# final_mouse.net
KiCad netlist of a schematic drawn in EAGLE
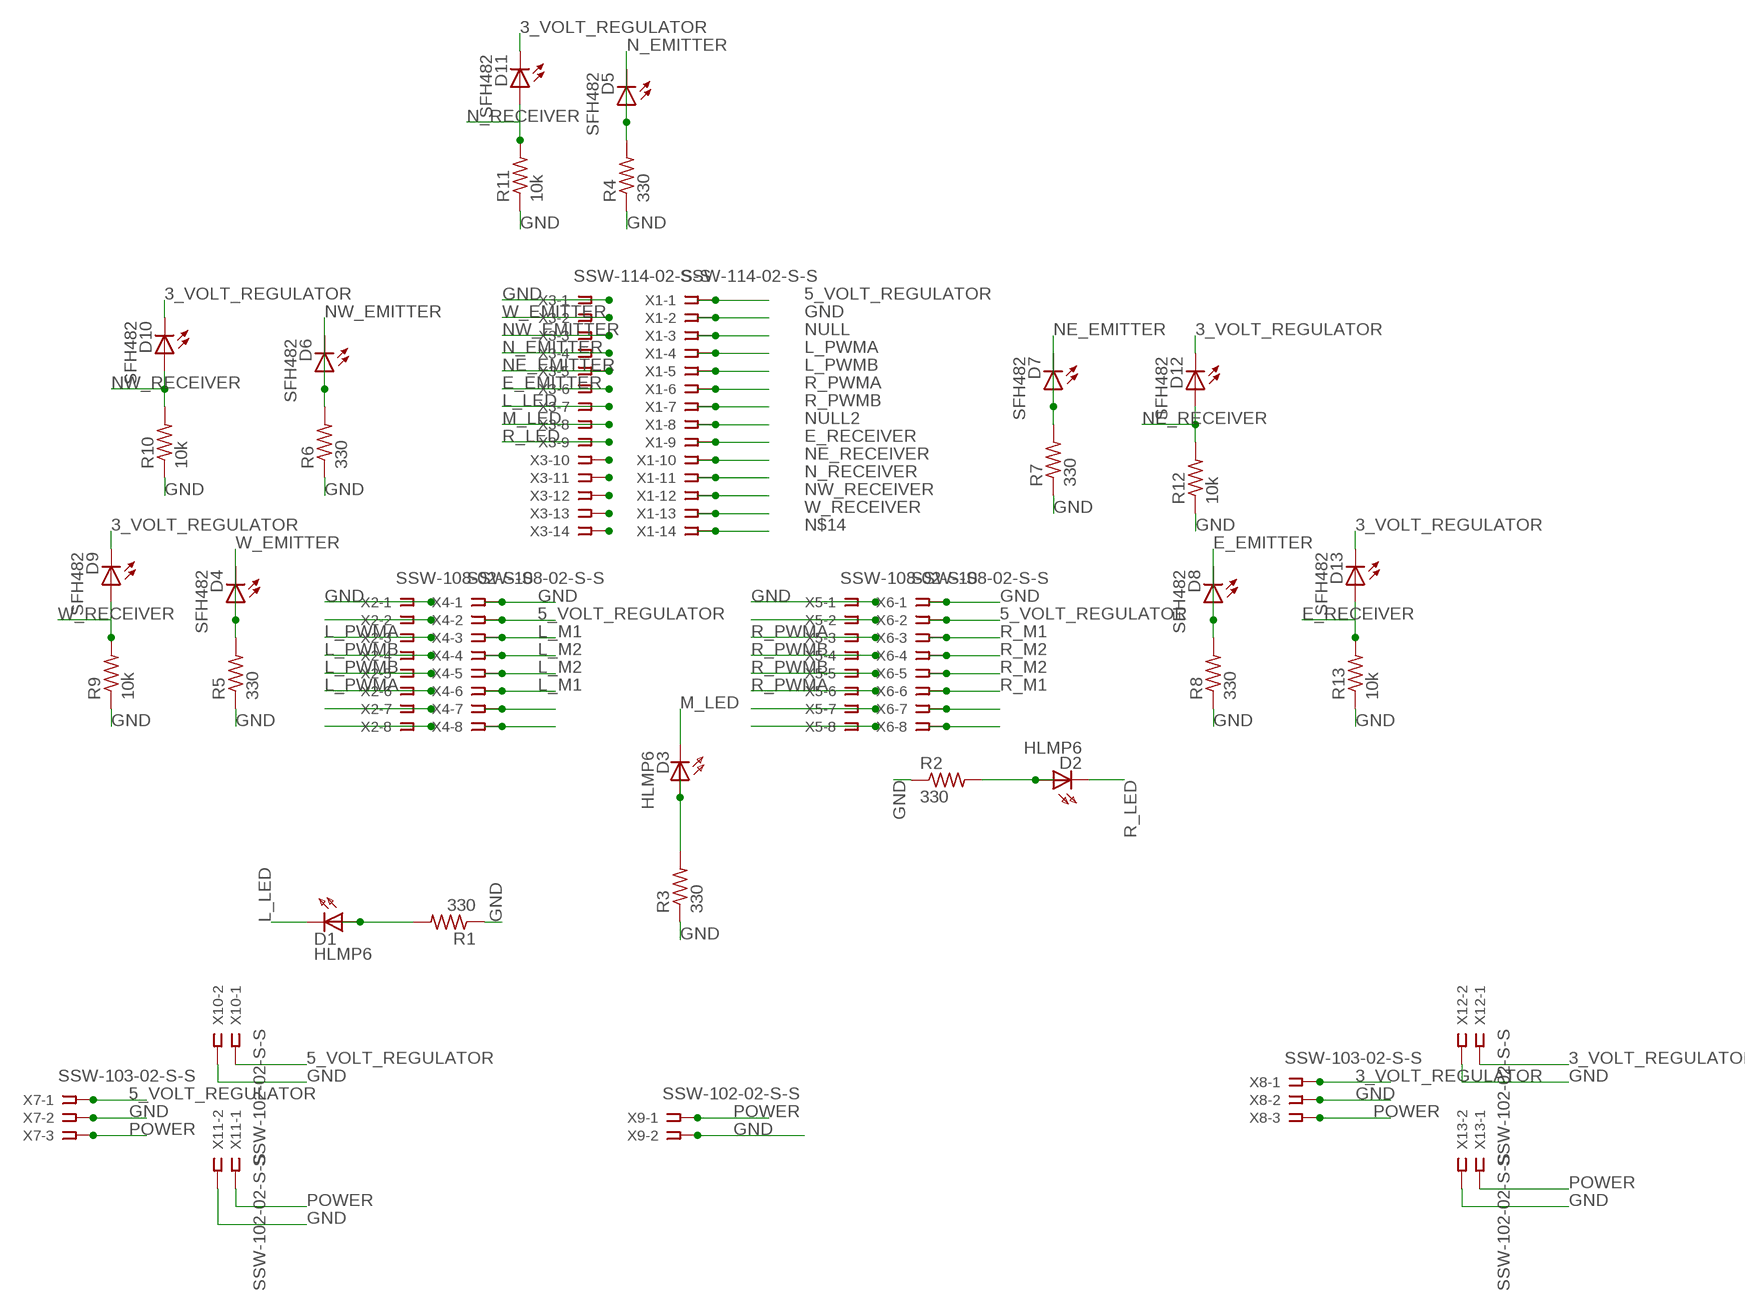
[diagram p0: schematic, sheet 1]

(export (version "E")
  (design (tool "Eeschema 10.0.6"))
  (components
    (comp (ref "D1")
      (value "HLMP6")
      (footprint "eagle-import:HLMP6")
      (fields (field (name "MF") "AGILENT TECHNOLOGIES") (field (name "MPN") "HLMP-6500"))
      (libsource (lib "eagle-import") (part "HLMP6"))
    )
    (comp (ref "D2")
      (value "HLMP6")
      (footprint "eagle-import:HLMP6")
      (fields (field (name "MF") "AGILENT TECHNOLOGIES") (field (name "MPN") "HLMP-6500"))
      (libsource (lib "eagle-import") (part "HLMP6"))
    )
    (comp (ref "D3")
      (value "HLMP6")
      (footprint "eagle-import:HLMP6")
      (fields (field (name "MF") "AGILENT TECHNOLOGIES") (field (name "MPN") "HLMP-6500"))
      (libsource (lib "eagle-import") (part "HLMP6"))
    )
    (comp (ref "D4")
      (value "SFH482")
      (footprint "eagle-import:SFH482")
      (libsource (lib "eagle-import") (part "SFH482"))
    )
    (comp (ref "D5")
      (value "SFH482")
      (footprint "eagle-import:SFH482")
      (libsource (lib "eagle-import") (part "SFH482"))
    )
    (comp (ref "D6")
      (value "SFH482")
      (footprint "eagle-import:SFH482")
      (libsource (lib "eagle-import") (part "SFH482"))
    )
    (comp (ref "D7")
      (value "SFH482")
      (footprint "eagle-import:SFH482")
      (libsource (lib "eagle-import") (part "SFH482"))
    )
    (comp (ref "D8")
      (value "SFH482")
      (footprint "eagle-import:SFH482")
      (libsource (lib "eagle-import") (part "SFH482"))
    )
    (comp (ref "D9")
      (value "SFH482")
      (footprint "eagle-import:SFH482")
      (libsource (lib "eagle-import") (part "SFH482"))
    )
    (comp (ref "D10")
      (value "SFH482")
      (footprint "eagle-import:SFH482")
      (libsource (lib "eagle-import") (part "SFH482"))
    )
    (comp (ref "D11")
      (value "SFH482")
      (footprint "eagle-import:SFH482")
      (libsource (lib "eagle-import") (part "SFH482"))
    )
    (comp (ref "D12")
      (value "SFH482")
      (footprint "eagle-import:SFH482")
      (libsource (lib "eagle-import") (part "SFH482"))
    )
    (comp (ref "D13")
      (value "SFH482")
      (footprint "eagle-import:SFH482")
      (libsource (lib "eagle-import") (part "SFH482"))
    )
    (comp (ref "R1")
      (value "330")
      (footprint "eagle-import:0204V")
      (libsource (lib "eagle-import") (part "R-US_0204/2V"))
    )
    (comp (ref "R2")
      (value "330")
      (footprint "eagle-import:0204V")
      (libsource (lib "eagle-import") (part "R-US_0204/2V"))
    )
    (comp (ref "R3")
      (value "330")
      (footprint "eagle-import:0204V")
      (libsource (lib "eagle-import") (part "R-US_0204/2V"))
    )
    (comp (ref "R4")
      (value "330")
      (footprint "eagle-import:0204V")
      (libsource (lib "eagle-import") (part "R-US_0204/2V"))
    )
    (comp (ref "R5")
      (value "330")
      (footprint "eagle-import:0204V")
      (libsource (lib "eagle-import") (part "R-US_0204/2V"))
    )
    (comp (ref "R6")
      (value "330")
      (footprint "eagle-import:0204V")
      (libsource (lib "eagle-import") (part "R-US_0204/2V"))
    )
    (comp (ref "R7")
      (value "330")
      (footprint "eagle-import:0204V")
      (libsource (lib "eagle-import") (part "R-US_0204/2V"))
    )
    (comp (ref "R8")
      (value "330")
      (footprint "eagle-import:0204V")
      (libsource (lib "eagle-import") (part "R-US_0204/2V"))
    )
    (comp (ref "R9")
      (value "10k")
      (footprint "eagle-import:0204V")
      (libsource (lib "eagle-import") (part "R-US_0204/2V"))
    )
    (comp (ref "R10")
      (value "10k")
      (footprint "eagle-import:0204V")
      (libsource (lib "eagle-import") (part "R-US_0204/2V"))
    )
    (comp (ref "R11")
      (value "10k")
      (footprint "eagle-import:0204V")
      (libsource (lib "eagle-import") (part "R-US_0204/2V"))
    )
    (comp (ref "R12")
      (value "10k")
      (footprint "eagle-import:0204V")
      (libsource (lib "eagle-import") (part "R-US_0204/2V"))
    )
    (comp (ref "R13")
      (value "10k")
      (footprint "eagle-import:0204V")
      (libsource (lib "eagle-import") (part "R-US_0204/2V"))
    )
    (comp (ref "X1")
      (value "SSW-114-02-S-S")
      (footprint "eagle-import:SSW-114-02-S-S")
      (libsource (lib "eagle-import") (part "SSW-114-02-S-S"))
    )
    (comp (ref "X2")
      (value "SSW-108-02-S-S")
      (footprint "eagle-import:SSW-108-02-S-S")
      (libsource (lib "eagle-import") (part "SSW-108-02-S-S"))
    )
    (comp (ref "X3")
      (value "SSW-114-02-S-S")
      (footprint "eagle-import:SSW-114-02-S-S")
      (libsource (lib "eagle-import") (part "SSW-114-02-S-S"))
    )
    (comp (ref "X4")
      (value "SSW-108-02-S-S")
      (footprint "eagle-import:SSW-108-02-S-S")
      (libsource (lib "eagle-import") (part "SSW-108-02-S-S"))
    )
    (comp (ref "X5")
      (value "SSW-108-02-S-S")
      (footprint "eagle-import:SSW-108-02-S-S")
      (libsource (lib "eagle-import") (part "SSW-108-02-S-S"))
    )
    (comp (ref "X6")
      (value "SSW-108-02-S-S")
      (footprint "eagle-import:SSW-108-02-S-S")
      (libsource (lib "eagle-import") (part "SSW-108-02-S-S"))
    )
    (comp (ref "X7")
      (value "SSW-103-02-S-S")
      (footprint "eagle-import:SSW-103-02-S-S")
      (libsource (lib "eagle-import") (part "SSW-103-02-S-S"))
    )
    (comp (ref "X8")
      (value "SSW-103-02-S-S")
      (footprint "eagle-import:SSW-103-02-S-S")
      (libsource (lib "eagle-import") (part "SSW-103-02-S-S"))
    )
    (comp (ref "X9")
      (value "SSW-102-02-S-S")
      (footprint "eagle-import:SSW-102-02-S-S")
      (libsource (lib "eagle-import") (part "SSW-102-02-S-S"))
    )
    (comp (ref "X10")
      (value "SSW-102-02-S-S")
      (footprint "eagle-import:SSW-102-02-S-S")
      (libsource (lib "eagle-import") (part "SSW-102-02-S-S"))
    )
    (comp (ref "X11")
      (value "SSW-102-02-S-S")
      (footprint "eagle-import:SSW-102-02-S-S")
      (libsource (lib "eagle-import") (part "SSW-102-02-S-S"))
    )
    (comp (ref "X12")
      (value "SSW-102-02-S-S")
      (footprint "eagle-import:SSW-102-02-S-S")
      (libsource (lib "eagle-import") (part "SSW-102-02-S-S"))
    )
    (comp (ref "X13")
      (value "SSW-102-02-S-S")
      (footprint "eagle-import:SSW-102-02-S-S")
      (libsource (lib "eagle-import") (part "SSW-102-02-S-S"))
    )
  )
  (nets
    (net (code "1") (name "/3_VOLT_REGULATOR") (class "Default")
      (node (ref "D10") (pin "K") (pinfunction "C_K") (pintype "passive"))
      (node (ref "D11") (pin "K") (pinfunction "C_K") (pintype "passive"))
      (node (ref "D12") (pin "K") (pinfunction "C_K") (pintype "passive"))
      (node (ref "D13") (pin "K") (pinfunction "C_K") (pintype "passive"))
      (node (ref "D9") (pin "K") (pinfunction "C_K") (pintype "passive"))
      (node (ref "X12") (pin "1") (pinfunction "1_1") (pintype "passive"))
      (node (ref "X8") (pin "1") (pinfunction "1_1") (pintype "passive"))
    )
    (net (code "2") (name "/5_VOLT_REGULATOR") (class "Default")
      (node (ref "X1") (pin "1") (pinfunction "1_1") (pintype "passive"))
      (node (ref "X10") (pin "1") (pinfunction "1_1") (pintype "passive"))
      (node (ref "X4") (pin "2") (pinfunction "1_2") (pintype "passive"))
      (node (ref "X6") (pin "2") (pinfunction "1_2") (pintype "passive"))
      (node (ref "X7") (pin "1") (pinfunction "1_1") (pintype "passive"))
    )
    (net (code "3") (name "/E_EMITTER") (class "Default")
      (node (ref "D8") (pin "A") (pinfunction "A_A") (pintype "passive"))
      (node (ref "D8") (pin "K") (pinfunction "C_K") (pintype "passive"))
      (node (ref "R8") (pin "2") (pinfunction "2_2") (pintype "passive"))
      (node (ref "X3") (pin "6") (pinfunction "1_6") (pintype "passive"))
    )
    (net (code "4") (name "/E_RECEIVER") (class "Default")
      (node (ref "D13") (pin "A") (pinfunction "A_A") (pintype "passive"))
      (node (ref "R13") (pin "2") (pinfunction "2_2") (pintype "passive"))
      (node (ref "X1") (pin "9") (pinfunction "1_9") (pintype "passive"))
    )
    (net (code "5") (name "/GND") (class "Default")
      (node (ref "R1") (pin "1") (pinfunction "1_1") (pintype "passive"))
      (node (ref "R10") (pin "1") (pinfunction "1_1") (pintype "passive"))
      (node (ref "R11") (pin "1") (pinfunction "1_1") (pintype "passive"))
      (node (ref "R12") (pin "1") (pinfunction "1_1") (pintype "passive"))
      (node (ref "R13") (pin "1") (pinfunction "1_1") (pintype "passive"))
      (node (ref "R2") (pin "1") (pinfunction "1_1") (pintype "passive"))
      (node (ref "R3") (pin "1") (pinfunction "1_1") (pintype "passive"))
      (node (ref "R4") (pin "1") (pinfunction "1_1") (pintype "passive"))
      (node (ref "R5") (pin "1") (pinfunction "1_1") (pintype "passive"))
      (node (ref "R6") (pin "1") (pinfunction "1_1") (pintype "passive"))
      (node (ref "R7") (pin "1") (pinfunction "1_1") (pintype "passive"))
      (node (ref "R8") (pin "1") (pinfunction "1_1") (pintype "passive"))
      (node (ref "R9") (pin "1") (pinfunction "1_1") (pintype "passive"))
      (node (ref "X1") (pin "2") (pinfunction "1_2") (pintype "passive"))
      (node (ref "X10") (pin "2") (pinfunction "1_2") (pintype "passive"))
      (node (ref "X11") (pin "2") (pinfunction "1_2") (pintype "passive"))
      (node (ref "X12") (pin "2") (pinfunction "1_2") (pintype "passive"))
      (node (ref "X13") (pin "2") (pinfunction "1_2") (pintype "passive"))
      (node (ref "X2") (pin "1") (pinfunction "1_1") (pintype "passive"))
      (node (ref "X3") (pin "1") (pinfunction "1_1") (pintype "passive"))
      (node (ref "X4") (pin "1") (pinfunction "1_1") (pintype "passive"))
      (node (ref "X5") (pin "1") (pinfunction "1_1") (pintype "passive"))
      (node (ref "X6") (pin "1") (pinfunction "1_1") (pintype "passive"))
      (node (ref "X7") (pin "2") (pinfunction "1_2") (pintype "passive"))
      (node (ref "X8") (pin "2") (pinfunction "1_2") (pintype "passive"))
      (node (ref "X9") (pin "2") (pinfunction "1_2") (pintype "passive"))
    )
    (net (code "6") (name "/L_LED") (class "Default")
      (node (ref "D1") (pin "K") (pinfunction "K_K") (pintype "passive"))
      (node (ref "X3") (pin "7") (pinfunction "1_7") (pintype "passive"))
    )
    (net (code "7") (name "/L_M1") (class "Default")
      (node (ref "X4") (pin "3") (pinfunction "1_3") (pintype "passive"))
      (node (ref "X4") (pin "6") (pinfunction "1_6") (pintype "passive"))
    )
    (net (code "8") (name "/L_M2") (class "Default")
      (node (ref "X4") (pin "4") (pinfunction "1_4") (pintype "passive"))
      (node (ref "X4") (pin "5") (pinfunction "1_5") (pintype "passive"))
    )
    (net (code "9") (name "/L_PWMA") (class "Default")
      (node (ref "X1") (pin "4") (pinfunction "1_4") (pintype "passive"))
      (node (ref "X2") (pin "3") (pinfunction "1_3") (pintype "passive"))
      (node (ref "X2") (pin "6") (pinfunction "1_6") (pintype "passive"))
    )
    (net (code "10") (name "/L_PWMB") (class "Default")
      (node (ref "X1") (pin "5") (pinfunction "1_5") (pintype "passive"))
      (node (ref "X2") (pin "4") (pinfunction "1_4") (pintype "passive"))
      (node (ref "X2") (pin "5") (pinfunction "1_5") (pintype "passive"))
    )
    (net (code "11") (name "/M_LED") (class "Default")
      (node (ref "D3") (pin "K") (pinfunction "K_K") (pintype "passive"))
      (node (ref "X3") (pin "8") (pinfunction "1_8") (pintype "passive"))
    )
    (net (code "12") (name "/N$14") (class "Default")
      (node (ref "X1") (pin "14") (pinfunction "1_14") (pintype "passive"))
    )
    (net (code "13") (name "/NE_EMITTER") (class "Default")
      (node (ref "D7") (pin "A") (pinfunction "A_A") (pintype "passive"))
      (node (ref "D7") (pin "K") (pinfunction "C_K") (pintype "passive"))
      (node (ref "R7") (pin "2") (pinfunction "2_2") (pintype "passive"))
      (node (ref "X3") (pin "5") (pinfunction "1_5") (pintype "passive"))
    )
    (net (code "14") (name "/NE_RECEIVER") (class "Default")
      (node (ref "D12") (pin "A") (pinfunction "A_A") (pintype "passive"))
      (node (ref "R12") (pin "2") (pinfunction "2_2") (pintype "passive"))
      (node (ref "X1") (pin "10") (pinfunction "1_10") (pintype "passive"))
    )
    (net (code "15") (name "/NULL") (class "Default")
      (node (ref "X1") (pin "3") (pinfunction "1_3") (pintype "passive"))
    )
    (net (code "16") (name "/NULL2") (class "Default")
      (node (ref "X1") (pin "8") (pinfunction "1_8") (pintype "passive"))
    )
    (net (code "17") (name "/NW_EMITTER") (class "Default")
      (node (ref "D6") (pin "A") (pinfunction "A_A") (pintype "passive"))
      (node (ref "D6") (pin "K") (pinfunction "C_K") (pintype "passive"))
      (node (ref "R6") (pin "2") (pinfunction "2_2") (pintype "passive"))
      (node (ref "X3") (pin "3") (pinfunction "1_3") (pintype "passive"))
    )
    (net (code "18") (name "/NW_RECEIVER") (class "Default")
      (node (ref "D10") (pin "A") (pinfunction "A_A") (pintype "passive"))
      (node (ref "R10") (pin "2") (pinfunction "2_2") (pintype "passive"))
      (node (ref "X1") (pin "12") (pinfunction "1_12") (pintype "passive"))
    )
    (net (code "19") (name "/N_EMITTER") (class "Default")
      (node (ref "D5") (pin "A") (pinfunction "A_A") (pintype "passive"))
      (node (ref "D5") (pin "K") (pinfunction "C_K") (pintype "passive"))
      (node (ref "R4") (pin "2") (pinfunction "2_2") (pintype "passive"))
      (node (ref "X3") (pin "4") (pinfunction "1_4") (pintype "passive"))
    )
    (net (code "20") (name "/N_RECEIVER") (class "Default")
      (node (ref "D11") (pin "A") (pinfunction "A_A") (pintype "passive"))
      (node (ref "R11") (pin "2") (pinfunction "2_2") (pintype "passive"))
      (node (ref "X1") (pin "11") (pinfunction "1_11") (pintype "passive"))
    )
    (net (code "21") (name "/POWER") (class "Default")
      (node (ref "X11") (pin "1") (pinfunction "1_1") (pintype "passive"))
      (node (ref "X13") (pin "1") (pinfunction "1_1") (pintype "passive"))
      (node (ref "X7") (pin "3") (pinfunction "1_3") (pintype "passive"))
      (node (ref "X8") (pin "3") (pinfunction "1_3") (pintype "passive"))
      (node (ref "X9") (pin "1") (pinfunction "1_1") (pintype "passive"))
    )
    (net (code "22") (name "/R_LED") (class "Default")
      (node (ref "D2") (pin "K") (pinfunction "K_K") (pintype "passive"))
      (node (ref "X3") (pin "9") (pinfunction "1_9") (pintype "passive"))
    )
    (net (code "23") (name "/R_M1") (class "Default")
      (node (ref "X6") (pin "3") (pinfunction "1_3") (pintype "passive"))
      (node (ref "X6") (pin "6") (pinfunction "1_6") (pintype "passive"))
    )
    (net (code "24") (name "/R_M2") (class "Default")
      (node (ref "X6") (pin "4") (pinfunction "1_4") (pintype "passive"))
      (node (ref "X6") (pin "5") (pinfunction "1_5") (pintype "passive"))
    )
    (net (code "25") (name "/R_PWMA") (class "Default")
      (node (ref "X1") (pin "6") (pinfunction "1_6") (pintype "passive"))
      (node (ref "X5") (pin "3") (pinfunction "1_3") (pintype "passive"))
      (node (ref "X5") (pin "6") (pinfunction "1_6") (pintype "passive"))
    )
    (net (code "26") (name "/R_PWMB") (class "Default")
      (node (ref "X1") (pin "7") (pinfunction "1_7") (pintype "passive"))
      (node (ref "X5") (pin "4") (pinfunction "1_4") (pintype "passive"))
      (node (ref "X5") (pin "5") (pinfunction "1_5") (pintype "passive"))
    )
    (net (code "27") (name "/W_EMITTER") (class "Default")
      (node (ref "D4") (pin "A") (pinfunction "A_A") (pintype "passive"))
      (node (ref "D4") (pin "K") (pinfunction "C_K") (pintype "passive"))
      (node (ref "R5") (pin "2") (pinfunction "2_2") (pintype "passive"))
      (node (ref "X3") (pin "2") (pinfunction "1_2") (pintype "passive"))
    )
    (net (code "28") (name "/W_RECEIVER") (class "Default")
      (node (ref "D9") (pin "A") (pinfunction "A_A") (pintype "passive"))
      (node (ref "R9") (pin "2") (pinfunction "2_2") (pintype "passive"))
      (node (ref "X1") (pin "13") (pinfunction "1_13") (pintype "passive"))
    )
    (net (code "29") (name "Net-(D1-PadA)") (class "Default")
      (node (ref "D1") (pin "A") (pinfunction "A_A") (pintype "passive"))
      (node (ref "R1") (pin "2") (pinfunction "2_2") (pintype "passive"))
    )
    (net (code "30") (name "Net-(D2-PadA)") (class "Default")
      (node (ref "D2") (pin "A") (pinfunction "A_A") (pintype "passive"))
      (node (ref "R2") (pin "2") (pinfunction "2_2") (pintype "passive"))
    )
    (net (code "31") (name "Net-(D3-PadA)") (class "Default")
      (node (ref "D3") (pin "A") (pinfunction "A_A") (pintype "passive"))
      (node (ref "R3") (pin "2") (pinfunction "2_2") (pintype "passive"))
    )
    (net (code "32") (name "unconnected-(X2B-1-Pad2)") (class "Default")
      (node (ref "X2") (pin "2") (pinfunction "1_2") (pintype "passive"))
    )
    (net (code "33") (name "unconnected-(X2G-1-Pad7)") (class "Default")
      (node (ref "X2") (pin "7") (pinfunction "1_7") (pintype "passive"))
    )
    (net (code "34") (name "unconnected-(X2H-1-Pad8)") (class "Default")
      (node (ref "X2") (pin "8") (pinfunction "1_8") (pintype "passive"))
    )
    (net (code "35") (name "unconnected-(X3B-1-Pad10)") (class "Default")
      (node (ref "X3") (pin "10") (pinfunction "1_10") (pintype "passive"))
    )
    (net (code "36") (name "unconnected-(X3C-1-Pad11)") (class "Default")
      (node (ref "X3") (pin "11") (pinfunction "1_11") (pintype "passive"))
    )
    (net (code "37") (name "unconnected-(X3D-1-Pad12)") (class "Default")
      (node (ref "X3") (pin "12") (pinfunction "1_12") (pintype "passive"))
    )
    (net (code "38") (name "unconnected-(X3E-1-Pad13)") (class "Default")
      (node (ref "X3") (pin "13") (pinfunction "1_13") (pintype "passive"))
    )
    (net (code "39") (name "unconnected-(X3F-1-Pad14)") (class "Default")
      (node (ref "X3") (pin "14") (pinfunction "1_14") (pintype "passive"))
    )
    (net (code "40") (name "unconnected-(X4G-1-Pad7)") (class "Default")
      (node (ref "X4") (pin "7") (pinfunction "1_7") (pintype "passive"))
    )
    (net (code "41") (name "unconnected-(X4H-1-Pad8)") (class "Default")
      (node (ref "X4") (pin "8") (pinfunction "1_8") (pintype "passive"))
    )
    (net (code "42") (name "unconnected-(X5B-1-Pad2)") (class "Default")
      (node (ref "X5") (pin "2") (pinfunction "1_2") (pintype "passive"))
    )
    (net (code "43") (name "unconnected-(X5G-1-Pad7)") (class "Default")
      (node (ref "X5") (pin "7") (pinfunction "1_7") (pintype "passive"))
    )
    (net (code "44") (name "unconnected-(X5H-1-Pad8)") (class "Default")
      (node (ref "X5") (pin "8") (pinfunction "1_8") (pintype "passive"))
    )
    (net (code "45") (name "unconnected-(X6G-1-Pad7)") (class "Default")
      (node (ref "X6") (pin "7") (pinfunction "1_7") (pintype "passive"))
    )
    (net (code "46") (name "unconnected-(X6H-1-Pad8)") (class "Default")
      (node (ref "X6") (pin "8") (pinfunction "1_8") (pintype "passive"))
    )
  )
)
